# ControllerDSP.net
KiCad netlist of a schematic drawn in Altium Designer
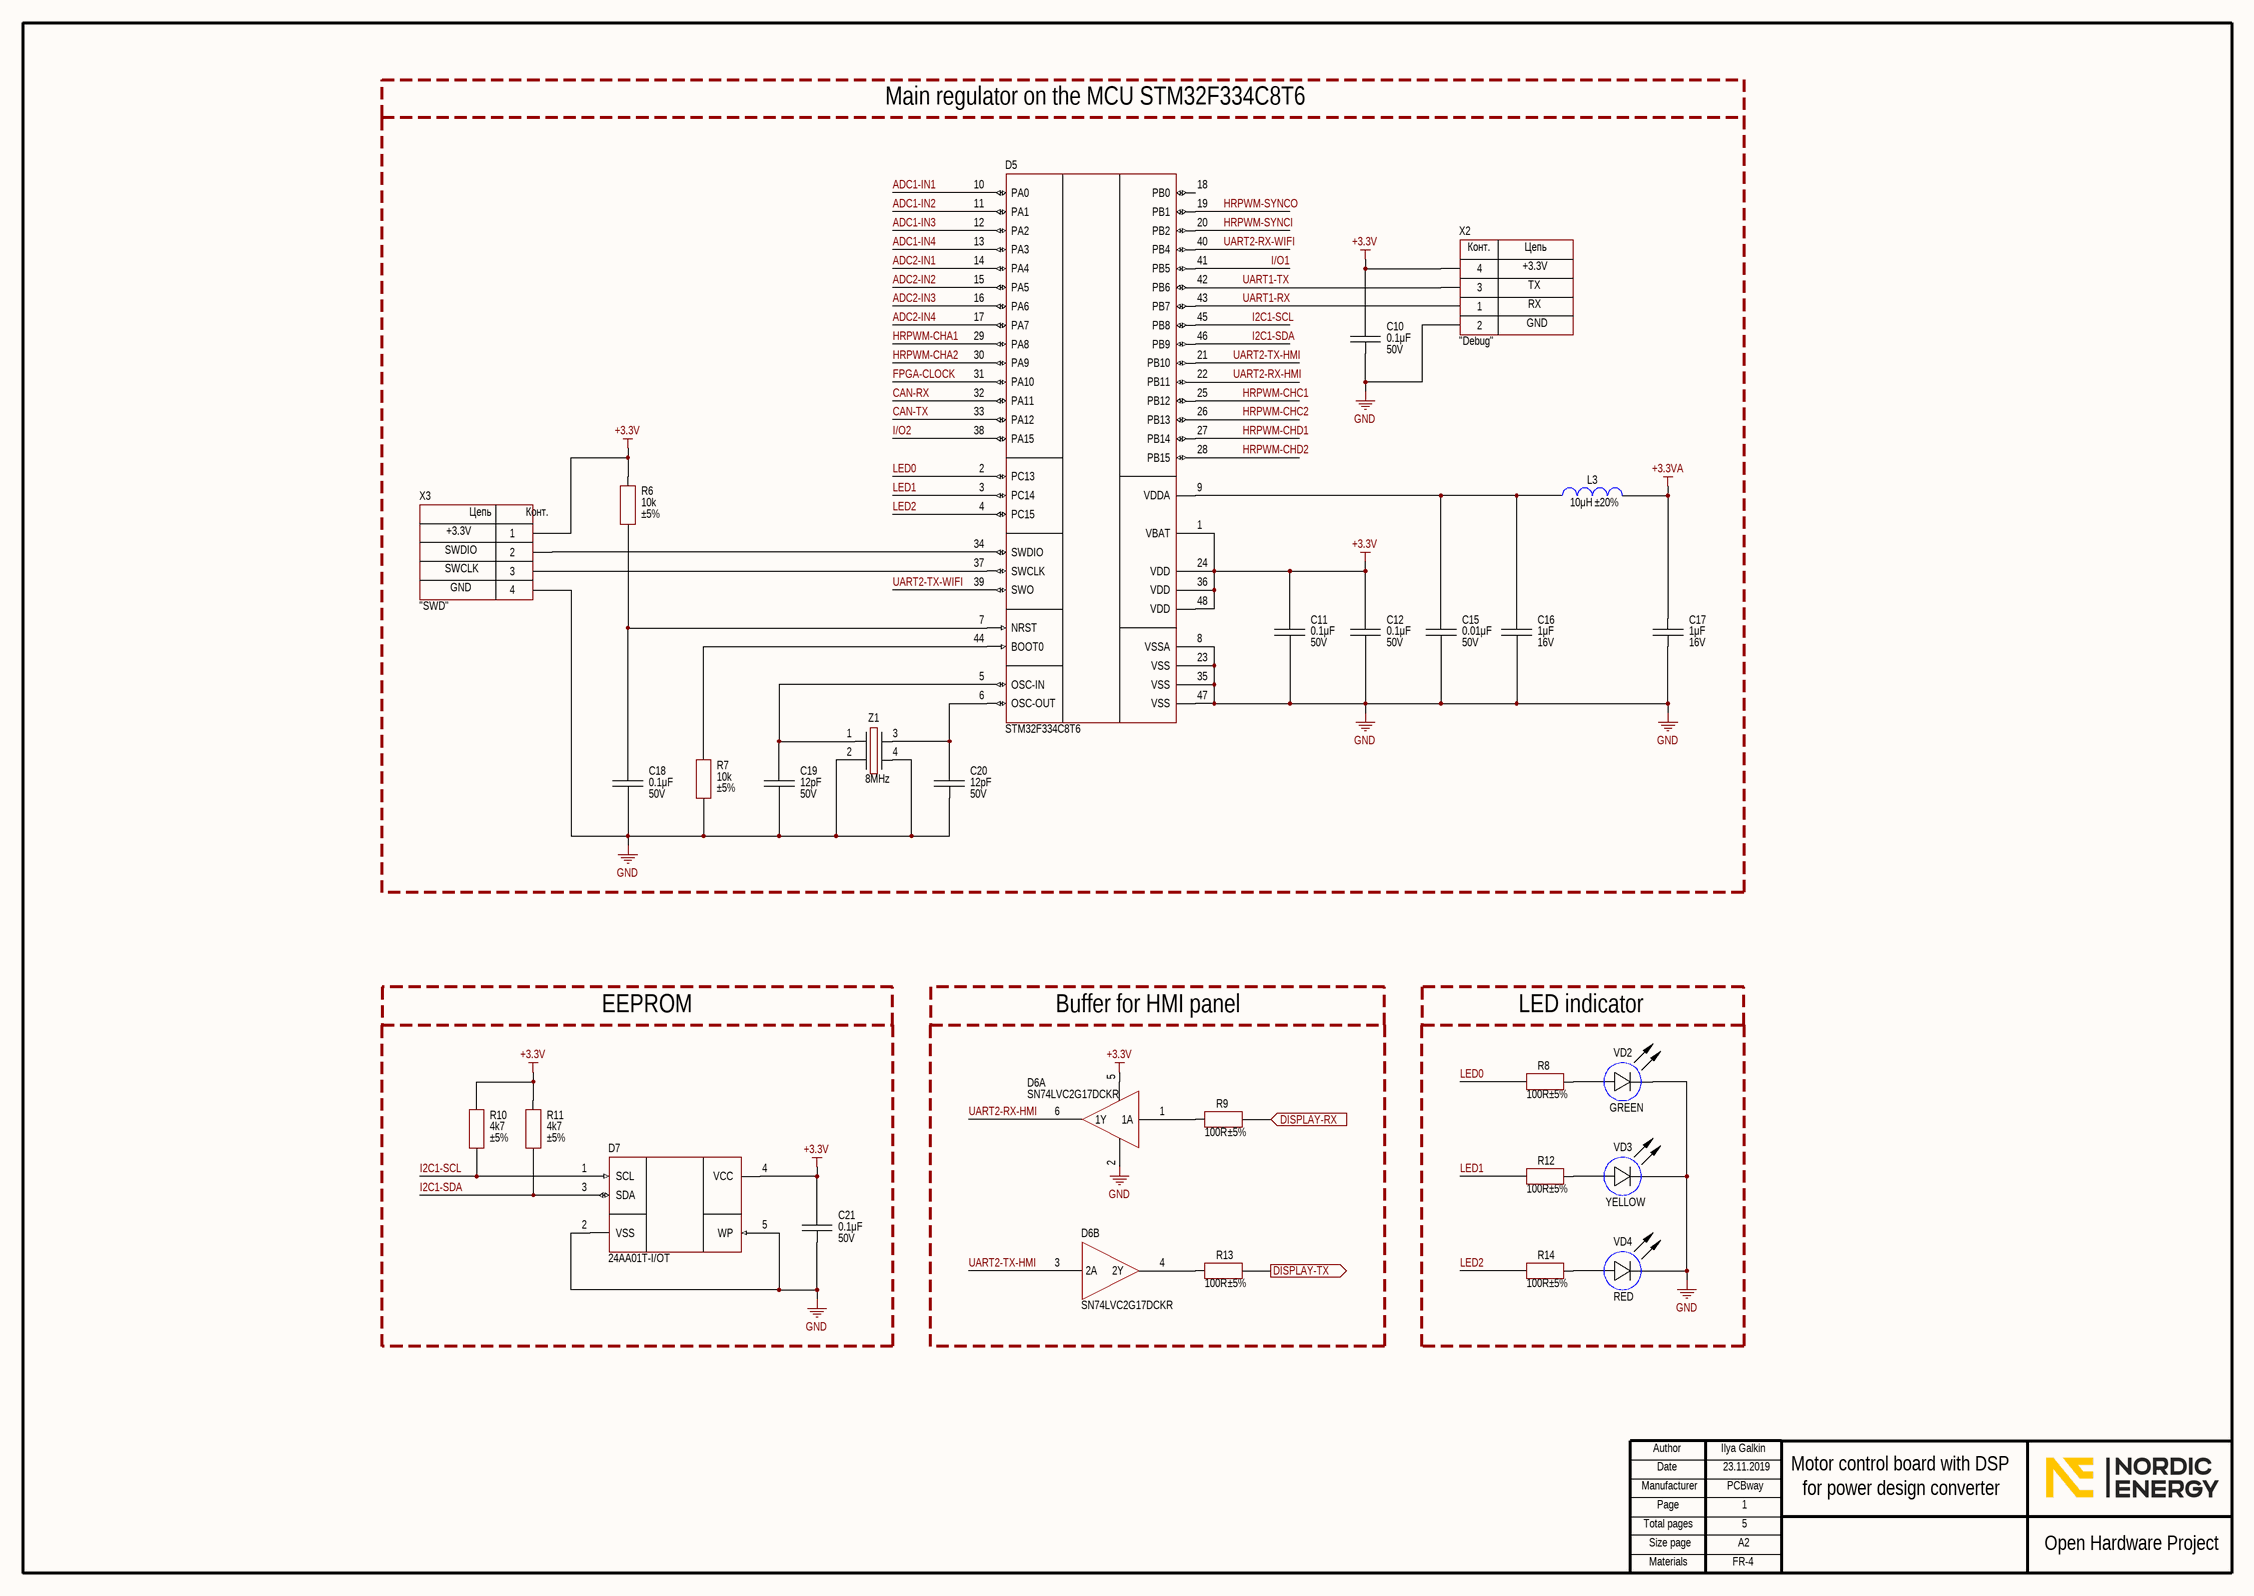
[diagram p0: ControllerDSP.SchDoc]

(export (version "E")
  (design (tool "Eeschema 10.0.6"))
  (components
    (comp (ref "C10")
      (value "0.1μF")
      (footprint "CAP: 0603")
      (fields
        (field (name "MANUFACTURER") "Samsung")
        (field (name "PARTNUMBER") "CL10B104KB8NNNC")
        (field (name "VALUEMANUFACTURERPARTNUMBER") "Ceramic capacitor, 0.1μF, X7R, ±10%, 50V, 0603, -55...+125°C")
        (field (name "VOLTAGE") "50V")
      )
      (libsource (lib "Capacitor") (part "Ceramic_0603"))
    )
    (comp (ref "C11")
      (value "0.1μF")
      (footprint "CAP: 0603")
      (fields
        (field (name "MANUFACTURER") "Samsung")
        (field (name "PARTNUMBER") "CL10B104KB8NNNC")
        (field (name "VALUEMANUFACTURERPARTNUMBER") "Ceramic capacitor, 0.1μF, X7R, ±10%, 50V, 0603, -55...+125°C")
        (field (name "VOLTAGE") "50V")
      )
      (libsource (lib "Capacitor") (part "Ceramic_0603"))
    )
    (comp (ref "C12")
      (value "0.1μF")
      (footprint "CAP: 0603")
      (fields
        (field (name "MANUFACTURER") "Samsung")
        (field (name "PARTNUMBER") "CL10B104KB8NNNC")
        (field (name "VALUEMANUFACTURERPARTNUMBER") "Ceramic capacitor, 0.1μF, X7R, ±10%, 50V, 0603, -55...+125°C")
        (field (name "VOLTAGE") "50V")
      )
      (libsource (lib "Capacitor") (part "Ceramic_0603"))
    )
    (comp (ref "C15")
      (value "0.01μF")
      (footprint "CAP: 0603")
      (fields
        (field (name "MANUFACTURER") "Samsung")
        (field (name "PARTNUMBER") "CL10B103KB8NNNC")
        (field (name "VALUEMANUFACTURERPARTNUMBER") "Ceramic capacitor, 0.01μF, X7R, ±10%, 50V, 0603, -55...+125°C")
        (field (name "VOLTAGE") "50V")
      )
      (libsource (lib "Capacitor") (part "Ceramic_0603"))
    )
    (comp (ref "C16")
      (value "1μF")
      (footprint "CAP: 0603")
      (fields
        (field (name "MANUFACTURER") "Samsung")
        (field (name "PARTNUMBER") "CL10B105KO8NNNC")
        (field (name "VALUEMANUFACTURERPARTNUMBER") "Ceramic capacitor, 1μF, X7R, ±10%, 16V, 0603, -55...+125°C")
        (field (name "VOLTAGE") "16V")
      )
      (libsource (lib "Capacitor") (part "Ceramic_0603"))
    )
    (comp (ref "C17")
      (value "1μF")
      (footprint "CAP: 0603")
      (fields
        (field (name "MANUFACTURER") "Samsung")
        (field (name "PARTNUMBER") "CL10B105KO8NNNC")
        (field (name "VALUEMANUFACTURERPARTNUMBER") "Ceramic capacitor, 1μF, X7R, ±10%, 16V, 0603, -55...+125°C")
        (field (name "VOLTAGE") "16V")
      )
      (libsource (lib "Capacitor") (part "Ceramic_0603"))
    )
    (comp (ref "C18")
      (value "0.1μF")
      (footprint "CAP: 0603")
      (fields
        (field (name "MANUFACTURER") "Samsung")
        (field (name "PARTNUMBER") "CL10B104KB8NNNC")
        (field (name "VALUEMANUFACTURERPARTNUMBER") "Ceramic capacitor, 0.1μF, X7R, ±10%, 50V, 0603, -55...+125°C")
        (field (name "VOLTAGE") "50V")
      )
      (libsource (lib "Capacitor") (part "Ceramic_0603"))
    )
    (comp (ref "C19")
      (value "12pF")
      (footprint "CAP: 0603")
      (fields
        (field (name "MANUFACTURER") "Samsung")
        (field (name "PARTNUMBER") "CL10C120JB8NNNC")
        (field (name "VALUEMANUFACTURERPARTNUMBER") "Ceramic capacitor, 12pF, NPO, ±10%, 50V, 0603, -55...+125°C")
        (field (name "VOLTAGE") "50V")
      )
      (libsource (lib "Capacitor") (part "Ceramic_0603"))
    )
    (comp (ref "C20")
      (value "12pF")
      (footprint "CAP: 0603")
      (fields
        (field (name "MANUFACTURER") "Samsung")
        (field (name "PARTNUMBER") "CL10C120JB8NNNC")
        (field (name "VALUEMANUFACTURERPARTNUMBER") "Ceramic capacitor, 12pF, NPO, ±10%, 50V, 0603, -55...+125°C")
        (field (name "VOLTAGE") "50V")
      )
      (libsource (lib "Capacitor") (part "Ceramic_0603"))
    )
    (comp (ref "C21")
      (value "0.1μF")
      (footprint "CAP: 0603")
      (fields
        (field (name "MANUFACTURER") "Samsung")
        (field (name "PARTNUMBER") "CL10B104KB8NNNC")
        (field (name "VALUEMANUFACTURERPARTNUMBER") "Ceramic capacitor, 0.1μF, X7R, ±10%, 50V, 0603, -55...+125°C")
        (field (name "VOLTAGE") "50V")
      )
      (libsource (lib "Capacitor") (part "Ceramic_0603"))
    )
    (comp (ref "D5")
      (value "~")
      (footprint "48-LQFP")
      (description "Cortex-M4")
      (fields
        (field (name "MANUFACTURER") "STMicroelectronics")
        (field (name "VALUEMANUFACTURERPARTNUMBER") "IC microcontroller, 32-Bit, Cortex-M4, 72MHz, 64KB, 12KB, 2...3.6V, -40...+85°C, 48-LQFP")
        (field (name "PARTNUMBER") "STM32F334C8T6")
      )
      (libsource (lib "IC. MCU") (part "STM32F334C8T6"))
    )
    (comp (ref "D6")
      (value "~")
      (footprint "SC70-6")
      (description "Buffer")
      (fields
        (field (name "MANUFACTURER") "Texas Instruments")
        (field (name "VALUEMANUFACTURERPARTNUMBER") "IC logic buffer, 1.65...5.5V, -40...+125°C, SC-70-6")
        (field (name "PARTNUMBER") "SN74LVC2G17DCKR")
      )
      (libsource (lib "IC. Logic") (part "SN74LVC2G17DCKR"))
    )
    (comp (ref "D7")
      (value "~")
      (footprint "SOT23-5")
      (description "EEPROM")
      (fields
        (field (name "MANUFACTURER") "Microchip Technology")
        (field (name "VALUEMANUFACTURERPARTNUMBER") "IC memory, EEPROM, 1KB (128x8), 400 kHz, I2C, 1.7...5.5V, -40...+85°C, SOT-23-5")
        (field (name "PARTNUMBER") "24AA01T-I/OT")
      )
      (libsource (lib "IC. Memory") (part "24AA01T"))
    )
    (comp (ref "L3")
      (value "10μH")
      (footprint "IND: 0603")
      (fields
        (field (name "MANUFACTURER") "Murata Electronics")
        (field (name "PARTNUMBER") "LQM18FN100M00D")
        (field (name "VALUEMANUFACTURERPARTNUMBER") "Fixed inductor, 10μH, ±20%, 0603, 50mA, -55...+125°C")
        (field (name "TOLERANCE") "±20%")
      )
      (libsource (lib "Inductor") (part "Inductor_0603"))
    )
    (comp (ref "R6")
      (value "10k")
      (footprint "RES: 0603")
      (fields
        (field (name "MANUFACTURER") "Yageo")
        (field (name "PARTNUMBER") "RC0603JR-0710KL")
        (field (name "VALUEMANUFACTURERPARTNUMBER") "Resistor film, 10k, ±5%, 0603, 0.1W, -55...+125°C")
        (field (name "TOLERANCE") "±5%")
      )
      (libsource (lib "Resistor") (part "Resistor_0603"))
    )
    (comp (ref "R7")
      (value "10k")
      (footprint "RES: 0603")
      (fields
        (field (name "MANUFACTURER") "Yageo")
        (field (name "PARTNUMBER") "RC0603JR-0710KL")
        (field (name "VALUEMANUFACTURERPARTNUMBER") "Resistor film, 10k, ±5%, 0603, 0.1W, -55...+125°C")
        (field (name "TOLERANCE") "±5%")
      )
      (libsource (lib "Resistor") (part "Resistor_0603"))
    )
    (comp (ref "R8")
      (value "100R")
      (footprint "RES: 0603")
      (fields
        (field (name "MANUFACTURER") "Yageo")
        (field (name "PARTNUMBER") "RC0603JR-07100RL")
        (field (name "VALUEMANUFACTURERPARTNUMBER") "Resistor film, 100R, ±5%, 0603, 0.1W, -55...+125°C")
        (field (name "TOLERANCE") "±5%")
      )
      (libsource (lib "") (part "Resistor_0603_1"))
    )
    (comp (ref "R9")
      (value "100R")
      (footprint "RES: 0603")
      (fields
        (field (name "MANUFACTURER") "Yageo")
        (field (name "PARTNUMBER") "RC0603JR-07100RL")
        (field (name "VALUEMANUFACTURERPARTNUMBER") "Resistor film, 100R, ±5%, 0603, 0.1W, -55...+125°C")
        (field (name "TOLERANCE") "±5%")
      )
      (libsource (lib "") (part "Resistor_0603_1"))
    )
    (comp (ref "R10")
      (value "4k7")
      (footprint "RES: 0603")
      (fields
        (field (name "MANUFACTURER") "Yageo")
        (field (name "PARTNUMBER") "RC0603JR-074K7L")
        (field (name "VALUEMANUFACTURERPARTNUMBER") "Resistor film, 4k7, ±5%, 0603, 0.1W, -55...+125°C")
        (field (name "TOLERANCE") "±5%")
      )
      (libsource (lib "Resistor") (part "Resistor_0603"))
    )
    (comp (ref "R11")
      (value "4k7")
      (footprint "RES: 0603")
      (fields
        (field (name "MANUFACTURER") "Yageo")
        (field (name "PARTNUMBER") "RC0603JR-074K7L")
        (field (name "VALUEMANUFACTURERPARTNUMBER") "Resistor film, 4k7, ±5%, 0603, 0.1W, -55...+125°C")
        (field (name "TOLERANCE") "±5%")
      )
      (libsource (lib "Resistor") (part "Resistor_0603"))
    )
    (comp (ref "R12")
      (value "100R")
      (footprint "RES: 0603")
      (fields
        (field (name "MANUFACTURER") "Yageo")
        (field (name "PARTNUMBER") "RC0603JR-07100RL")
        (field (name "VALUEMANUFACTURERPARTNUMBER") "Resistor film, 100R, ±5%, 0603, 0.1W, -55...+125°C")
        (field (name "TOLERANCE") "±5%")
      )
      (libsource (lib "") (part "Resistor_0603_1"))
    )
    (comp (ref "R13")
      (value "100R")
      (footprint "RES: 0603")
      (fields
        (field (name "MANUFACTURER") "Yageo")
        (field (name "PARTNUMBER") "RC0603JR-07100RL")
        (field (name "VALUEMANUFACTURERPARTNUMBER") "Resistor film, 100R, ±5%, 0603, 0.1W, -55...+125°C")
        (field (name "TOLERANCE") "±5%")
      )
      (libsource (lib "") (part "Resistor_0603_1"))
    )
    (comp (ref "R14")
      (value "100R")
      (footprint "RES: 0603")
      (fields
        (field (name "MANUFACTURER") "Yageo")
        (field (name "PARTNUMBER") "RC0603JR-07100RL")
        (field (name "VALUEMANUFACTURERPARTNUMBER") "Resistor film, 100R, ±5%, 0603, 0.1W, -55...+125°C")
        (field (name "TOLERANCE") "±5%")
      )
      (libsource (lib "") (part "Resistor_0603_1"))
    )
    (comp (ref "VD2")
      (value "~")
      (footprint "LED: 0603G")
      (fields
        (field (name "MANUFACTURER") "Wurth")
        (field (name "VALUEMANUFACTURERPARTNUMBER") "LED, Green, 20mA, 2V, 0603, -55...+150°C")
        (field (name "PARTNUMBER") "150060VS75000")
        (field (name "COLOR") "GREEN")
      )
      (libsource (lib "Diode") (part "LED_single"))
    )
    (comp (ref "VD3")
      (value "~")
      (footprint "LED: 0603Y")
      (fields
        (field (name "MANUFACTURER") "Wurth")
        (field (name "VALUEMANUFACTURERPARTNUMBER") "LED, Yellow, 20mA, 2V, 0603, -55...+150°C")
        (field (name "PARTNUMBER") "150060YS75000")
        (field (name "COLOR") "YELLOW")
      )
      (libsource (lib "Diode") (part "LED_single"))
    )
    (comp (ref "VD4")
      (value "~")
      (footprint "LED: 0603R")
      (fields
        (field (name "MANUFACTURER") "Wurth")
        (field (name "VALUEMANUFACTURERPARTNUMBER") "LED, Red, 20mA, 2V, 0603, -55...+150°C")
        (field (name "PARTNUMBER") "150060RS55040")
        (field (name "COLOR") "RED")
      )
      (libsource (lib "Diode") (part "LED_single"))
    )
    (comp (ref "X2")
      (value "~")
      (footprint "CON: PBD-4")
      (fields
        (field (name "MANUFACTURER") "Connfly")
        (field (name "VALUEMANUFACTURERPARTNUMBER") "Connector, 4pin, 2.54mm, 500VAC, 3A")
        (field (name "PARTNUMBER") "PBD-4")
        (field (name "COMMENTTEXT") "\"Debug\"")
      )
      (libsource (lib "Connector") (part "Standard_Debug"))
    )
    (comp (ref "X3")
      (value "~")
      (footprint "CON: SM04B-GHS")
      (fields
        (field (name "MANUFACTURER") "JST")
        (field (name "VALUEMANUFACTURERPARTNUMBER") "Connector, 4pin, 1.25mm, 50VDC, 1A")
        (field (name "PARTNUMBER") "SM04B-GHS")
        (field (name "COMMENTTEXT") "\"SWD\"")
      )
      (libsource (lib "Connector") (part "Connector_SM04B"))
    )
    (comp (ref "Z1")
      (value "~")
      (footprint "OSC: 3225")
      (fields
        (field (name "MANUFACTURER") "Diodes Incorporated")
        (field (name "PARTNUMBER") "FL0800008Q")
        (field (name "VALUEMANUFACTURERPARTNUMBER") "Crystal, 8MHz, 12pF, ±30ppm, case 3225, -40...+85°C")
        (field (name "FREQUENCY") "8MHz")
      )
      (libsource (lib "Oscilator") (part "Crystal_3225"))
    )
  )
  (nets
    (net (code "1") (name "+3.3V") (class "Default")
      (node (ref "C10") (pin "2") (pinfunction "2_2") (pintype "power_in"))
      (node (ref "C11") (pin "2") (pinfunction "2_2") (pintype "power_in"))
      (node (ref "C12") (pin "2") (pinfunction "2_2") (pintype "power_in"))
      (node (ref "C21") (pin "2") (pinfunction "2_2") (pintype "power_in"))
      (node (ref "D5") (pin "1") (pinfunction "VBAT_1") (pintype "passive"))
      (node (ref "D5") (pin "24") (pinfunction "VDD_24") (pintype "passive"))
      (node (ref "D5") (pin "36") (pinfunction "VDD_36") (pintype "passive"))
      (node (ref "D5") (pin "48") (pinfunction "VDD_48") (pintype "passive"))
      (node (ref "D6") (pin "5") (pintype "passive"))
      (node (ref "D7") (pin "4") (pinfunction "VCC_4") (pintype "power_in"))
      (node (ref "R10") (pin "2") (pinfunction "2_2") (pintype "passive"))
      (node (ref "R11") (pin "2") (pinfunction "2_2") (pintype "passive"))
      (node (ref "R6") (pin "2") (pinfunction "2_2") (pintype "passive"))
      (node (ref "X2") (pin "4") (pinfunction "4_4") (pintype "power_in"))
      (node (ref "X3") (pin "1") (pinfunction "1_1") (pintype "passive"))
    )
    (net (code "2") (name "+3.3VA") (class "Default")
      (node (ref "C17") (pin "2") (pinfunction "2_2") (pintype "power_in"))
      (node (ref "L3") (pin "1") (pinfunction "1_1") (pintype "passive"))
    )
    (net (code "3") (name "/ADC1-IN1") (class "Default")
      (node (ref "D5") (pin "10") (pinfunction "PA0_10") (pintype "bidirectional"))
    )
    (net (code "4") (name "/ADC1-IN2") (class "Default")
      (node (ref "D5") (pin "11") (pinfunction "PA1_11") (pintype "bidirectional"))
    )
    (net (code "5") (name "/ADC1-IN3") (class "Default")
      (node (ref "D5") (pin "12") (pinfunction "PA2_12") (pintype "bidirectional"))
    )
    (net (code "6") (name "/ADC1-IN4") (class "Default")
      (node (ref "D5") (pin "13") (pinfunction "PA3_13") (pintype "bidirectional"))
    )
    (net (code "7") (name "/ADC2-IN1") (class "Default")
      (node (ref "D5") (pin "14") (pinfunction "PA4_14") (pintype "bidirectional"))
    )
    (net (code "8") (name "/ADC2-IN2") (class "Default")
      (node (ref "D5") (pin "15") (pinfunction "PA5_15") (pintype "bidirectional"))
    )
    (net (code "9") (name "/ADC2-IN3") (class "Default")
      (node (ref "D5") (pin "16") (pinfunction "PA6_16") (pintype "bidirectional"))
    )
    (net (code "10") (name "/ADC2-IN4") (class "Default")
      (node (ref "D5") (pin "17") (pinfunction "PA7_17") (pintype "bidirectional"))
    )
    (net (code "11") (name "/CAN-RX") (class "Default")
      (node (ref "D5") (pin "32") (pinfunction "PA11_32") (pintype "bidirectional"))
    )
    (net (code "12") (name "/CAN-TX") (class "Default")
      (node (ref "D5") (pin "33") (pinfunction "PA12_33") (pintype "bidirectional"))
    )
    (net (code "13") (name "/DISPLAY-RX") (class "Default")
      (node (ref "R9") (pin "2") (pinfunction "2_2") (pintype "passive"))
    )
    (net (code "14") (name "/DISPLAY-TX") (class "Default")
      (node (ref "R13") (pin "2") (pinfunction "2_2") (pintype "passive"))
    )
    (net (code "15") (name "/FPGA-CLOCK") (class "Default")
      (node (ref "D5") (pin "31") (pinfunction "PA10_31") (pintype "bidirectional"))
    )
    (net (code "16") (name "/HRPWM-CHA1") (class "Default")
      (node (ref "D5") (pin "29") (pinfunction "PA8_29") (pintype "bidirectional"))
    )
    (net (code "17") (name "/HRPWM-CHA2") (class "Default")
      (node (ref "D5") (pin "30") (pinfunction "PA9_30") (pintype "bidirectional"))
    )
    (net (code "18") (name "/HRPWM-CHC1") (class "Default")
      (node (ref "D5") (pin "25") (pinfunction "PB12_25") (pintype "bidirectional"))
    )
    (net (code "19") (name "/HRPWM-CHC2") (class "Default")
      (node (ref "D5") (pin "26") (pinfunction "PB13_26") (pintype "bidirectional"))
    )
    (net (code "20") (name "/HRPWM-CHD1") (class "Default")
      (node (ref "D5") (pin "27") (pinfunction "PB14_27") (pintype "bidirectional"))
    )
    (net (code "21") (name "/HRPWM-CHD2") (class "Default")
      (node (ref "D5") (pin "28") (pinfunction "PB15_28") (pintype "bidirectional"))
    )
    (net (code "22") (name "/HRPWM-SYNCI") (class "Default")
      (node (ref "D5") (pin "20") (pinfunction "PB2_20") (pintype "bidirectional"))
    )
    (net (code "23") (name "/HRPWM-SYNCO") (class "Default")
      (node (ref "D5") (pin "19") (pinfunction "PB1_19") (pintype "bidirectional"))
    )
    (net (code "24") (name "/I2C1-SCL") (class "Default")
      (node (ref "D5") (pin "45") (pinfunction "PB8_45") (pintype "bidirectional"))
      (node (ref "D7") (pin "1") (pinfunction "SCL_1") (pintype "input"))
      (node (ref "R10") (pin "1") (pinfunction "1_1") (pintype "passive"))
    )
    (net (code "25") (name "/I2C1-SDA") (class "Default")
      (node (ref "D5") (pin "46") (pinfunction "PB9_46") (pintype "bidirectional"))
      (node (ref "D7") (pin "3") (pinfunction "SDA_3") (pintype "bidirectional"))
      (node (ref "R11") (pin "1") (pinfunction "1_1") (pintype "passive"))
    )
    (net (code "26") (name "/I{slash}O1") (class "Default")
      (node (ref "D5") (pin "41") (pinfunction "PB5_41") (pintype "bidirectional"))
    )
    (net (code "27") (name "/I{slash}O2") (class "Default")
      (node (ref "D5") (pin "38") (pinfunction "PA15_38") (pintype "bidirectional"))
    )
    (net (code "28") (name "/LED0") (class "Default")
      (node (ref "D5") (pin "2") (pinfunction "PC13_2") (pintype "bidirectional"))
      (node (ref "R8") (pin "1") (pinfunction "1_1") (pintype "passive"))
    )
    (net (code "29") (name "/LED1") (class "Default")
      (node (ref "D5") (pin "3") (pinfunction "PC14_3") (pintype "bidirectional"))
      (node (ref "R12") (pin "1") (pinfunction "1_1") (pintype "passive"))
    )
    (net (code "30") (name "/LED2") (class "Default")
      (node (ref "D5") (pin "4") (pinfunction "PC15_4") (pintype "bidirectional"))
      (node (ref "R14") (pin "1") (pinfunction "1_1") (pintype "passive"))
    )
    (net (code "31") (name "/UART1-RX") (class "Default")
      (node (ref "D5") (pin "43") (pinfunction "PB7_43") (pintype "bidirectional"))
      (node (ref "X2") (pin "1") (pinfunction "1_1") (pintype "passive"))
    )
    (net (code "32") (name "/UART1-TX") (class "Default")
      (node (ref "D5") (pin "42") (pinfunction "PB6_42") (pintype "bidirectional"))
      (node (ref "X2") (pin "3") (pinfunction "3_3") (pintype "power_in"))
    )
    (net (code "33") (name "/UART2-RX-HMI") (class "Default")
      (node (ref "D5") (pin "22") (pinfunction "PB11_22") (pintype "bidirectional"))
      (node (ref "D6") (pin "6") (pinfunction "1Y_6") (pintype "passive"))
    )
    (net (code "34") (name "/UART2-RX-WIFI") (class "Default")
      (node (ref "D5") (pin "40") (pinfunction "PB4_40") (pintype "bidirectional"))
    )
    (net (code "35") (name "/UART2-TX-HMI") (class "Default")
      (node (ref "D5") (pin "21") (pinfunction "PB10_21") (pintype "bidirectional"))
      (node (ref "D6") (pin "3") (pinfunction "2A_3") (pintype "passive"))
    )
    (net (code "36") (name "/UART2-TX-WIFI") (class "Default")
      (node (ref "D5") (pin "39") (pinfunction "SWO_39") (pintype "bidirectional"))
    )
    (net (code "37") (name "GND") (class "Default")
      (node (ref "C10") (pin "1") (pinfunction "1_1") (pintype "power_in"))
      (node (ref "C11") (pin "1") (pinfunction "1_1") (pintype "power_in"))
      (node (ref "C12") (pin "1") (pinfunction "1_1") (pintype "power_in"))
      (node (ref "C15") (pin "1") (pinfunction "1_1") (pintype "power_in"))
      (node (ref "C16") (pin "1") (pinfunction "1_1") (pintype "power_in"))
      (node (ref "C17") (pin "1") (pinfunction "1_1") (pintype "power_in"))
      (node (ref "C18") (pin "1") (pinfunction "1_1") (pintype "power_in"))
      (node (ref "C19") (pin "1") (pinfunction "1_1") (pintype "power_in"))
      (node (ref "C20") (pin "1") (pinfunction "1_1") (pintype "power_in"))
      (node (ref "C21") (pin "1") (pinfunction "1_1") (pintype "power_in"))
      (node (ref "D5") (pin "23") (pinfunction "VSS_23") (pintype "passive"))
      (node (ref "D5") (pin "35") (pinfunction "VSS_35") (pintype "passive"))
      (node (ref "D5") (pin "47") (pinfunction "VSS_47") (pintype "passive"))
      (node (ref "D5") (pin "8") (pinfunction "VSSA_8") (pintype "passive"))
      (node (ref "D6") (pin "2") (pintype "passive"))
      (node (ref "D7") (pin "2") (pinfunction "VSS_2") (pintype "power_in"))
      (node (ref "D7") (pin "5") (pinfunction "WP_5") (pintype "input"))
      (node (ref "R7") (pin "1") (pinfunction "1_1") (pintype "passive"))
      (node (ref "VD2") (pin "2") (pinfunction "C_2") (pintype "passive"))
      (node (ref "VD3") (pin "2") (pinfunction "C_2") (pintype "passive"))
      (node (ref "VD4") (pin "2") (pinfunction "C_2") (pintype "passive"))
      (node (ref "X2") (pin "2") (pinfunction "2_2") (pintype "passive"))
      (node (ref "X3") (pin "4") (pinfunction "4_4") (pintype "power_in"))
      (node (ref "Z1") (pin "2") (pinfunction "2_2") (pintype "passive"))
      (node (ref "Z1") (pin "4") (pinfunction "4_4") (pintype "passive"))
    )
    (net (code "38") (name "Net-(D5-BOOT0)") (class "Default")
      (node (ref "D5") (pin "44") (pinfunction "BOOT0_44") (pintype "input"))
      (node (ref "R7") (pin "2") (pinfunction "2_2") (pintype "passive"))
    )
    (net (code "39") (name "Net-(D5-NRST)") (class "Default")
      (node (ref "C18") (pin "2") (pinfunction "2_2") (pintype "power_in"))
      (node (ref "D5") (pin "7") (pinfunction "NRST_7") (pintype "input"))
      (node (ref "R6") (pin "1") (pinfunction "1_1") (pintype "passive"))
    )
    (net (code "40") (name "Net-(D5-OSC-IN)") (class "Default")
      (node (ref "C19") (pin "2") (pinfunction "2_2") (pintype "power_in"))
      (node (ref "D5") (pin "5") (pinfunction "OSC-IN_5") (pintype "bidirectional"))
      (node (ref "Z1") (pin "1") (pinfunction "1_1") (pintype "passive"))
    )
    (net (code "41") (name "Net-(D5-OSC-OUT)") (class "Default")
      (node (ref "C20") (pin "2") (pinfunction "2_2") (pintype "power_in"))
      (node (ref "D5") (pin "6") (pinfunction "OSC-OUT_6") (pintype "bidirectional"))
      (node (ref "Z1") (pin "3") (pinfunction "3_3") (pintype "passive"))
    )
    (net (code "42") (name "Net-(D5-SWCLK)") (class "Default")
      (node (ref "D5") (pin "37") (pinfunction "SWCLK_37") (pintype "bidirectional"))
      (node (ref "X3") (pin "3") (pinfunction "3_3") (pintype "power_in"))
    )
    (net (code "43") (name "Net-(D5-SWDIO)") (class "Default")
      (node (ref "D5") (pin "34") (pinfunction "SWDIO_34") (pintype "bidirectional"))
      (node (ref "X3") (pin "2") (pinfunction "2_2") (pintype "passive"))
    )
    (net (code "44") (name "Net-(D5-VDDA)") (class "Default")
      (node (ref "C15") (pin "2") (pinfunction "2_2") (pintype "power_in"))
      (node (ref "C16") (pin "2") (pinfunction "2_2") (pintype "power_in"))
      (node (ref "D5") (pin "9") (pinfunction "VDDA_9") (pintype "passive"))
      (node (ref "L3") (pin "2") (pinfunction "2_2") (pintype "passive"))
    )
    (net (code "45") (name "Net-(D6A-1A)") (class "Default")
      (node (ref "D6") (pin "1") (pinfunction "1A_1") (pintype "passive"))
      (node (ref "R9") (pin "1") (pinfunction "1_1") (pintype "passive"))
    )
    (net (code "46") (name "Net-(D6B-2Y)") (class "Default")
      (node (ref "D6") (pin "4") (pinfunction "2Y_4") (pintype "passive"))
      (node (ref "R13") (pin "1") (pinfunction "1_1") (pintype "passive"))
    )
    (net (code "47") (name "Net-(VD2-A)") (class "Default")
      (node (ref "R8") (pin "2") (pinfunction "2_2") (pintype "passive"))
      (node (ref "VD2") (pin "1") (pinfunction "A_1") (pintype "passive"))
    )
    (net (code "48") (name "Net-(VD3-A)") (class "Default")
      (node (ref "R12") (pin "2") (pinfunction "2_2") (pintype "passive"))
      (node (ref "VD3") (pin "1") (pinfunction "A_1") (pintype "passive"))
    )
    (net (code "49") (name "Net-(VD4-A)") (class "Default")
      (node (ref "R14") (pin "2") (pinfunction "2_2") (pintype "passive"))
      (node (ref "VD4") (pin "1") (pinfunction "A_1") (pintype "passive"))
    )
    (net (code "50") (name "unconnected-(D5-PB0-Pad18)") (class "Default")
      (node (ref "D5") (pin "18") (pinfunction "PB0_18") (pintype "bidirectional"))
    )
  )
)
